# GPIO.net
KiCad netlist of a schematic drawn in Altium Designer
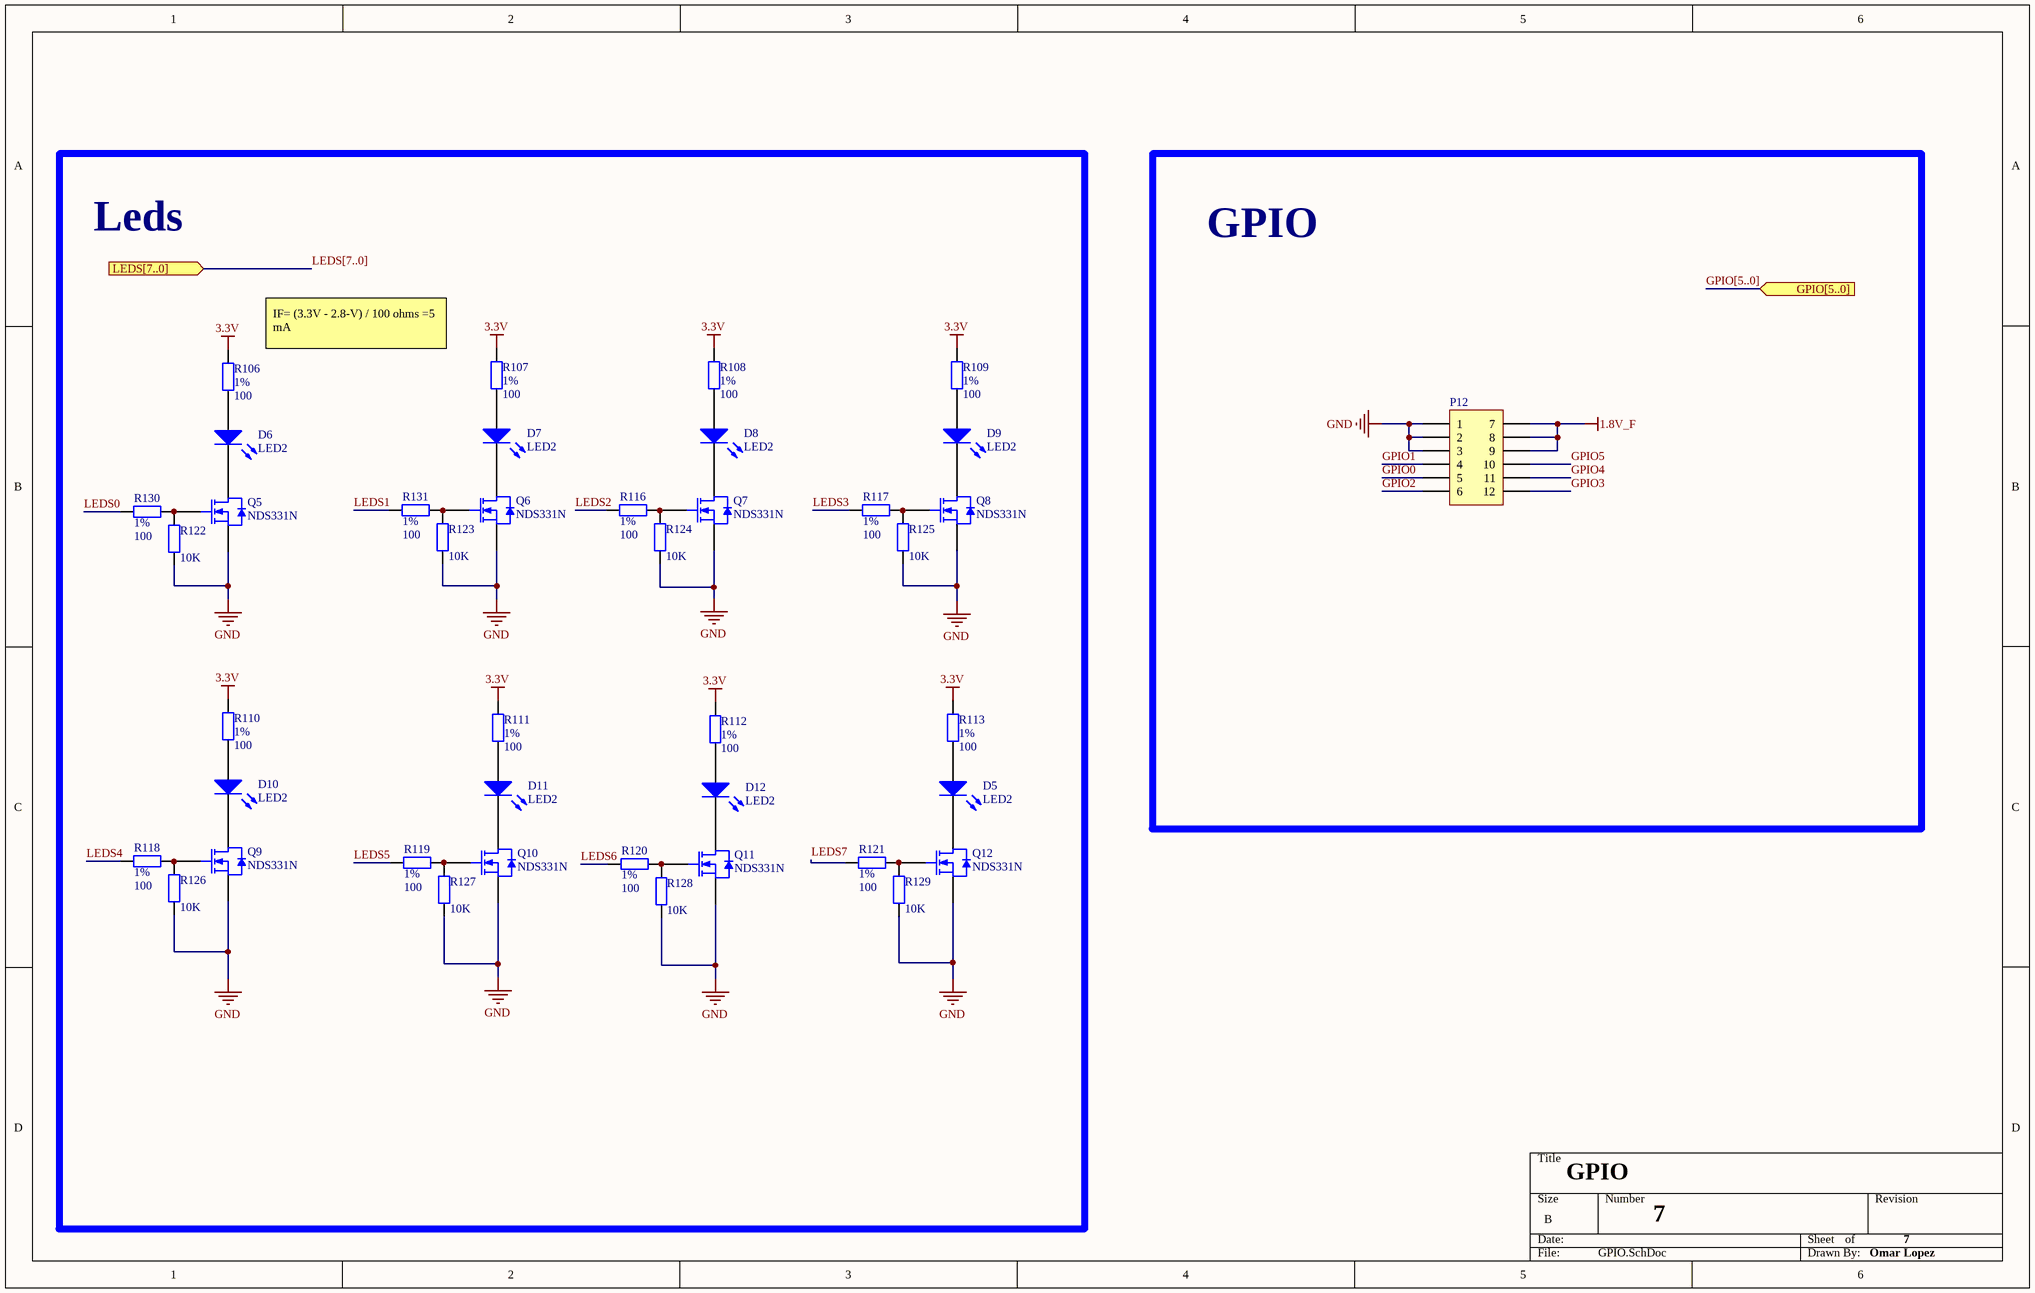
[diagram p0: GPIO.SchDoc]

(export (version "E")
  (design (tool "Eeschema 10.0.6"))
  (components
    (comp (ref "D5")
      (value "LED2")
      (footprint "LiteOnLed:LTSTC191")
      (description "Typical RED, GREEN, YELLOW, AMBER GaAs LED")
      (fields (field (name "MANUFACTURER") "Panasonic") (field (name "PARTNUMBER") "LTST-C193TGKT-5A"))
      (libsource (lib "Miscellaneous Devices") (part "LED2"))
    )
    (comp (ref "D6")
      (value "LED2")
      (footprint "LiteOnLed:LTSTC191")
      (description "Typical RED, GREEN, YELLOW, AMBER GaAs LED")
      (fields (field (name "MANUFACTURER") "Panasonic") (field (name "PARTNUMBER") "LTST-C193TGKT-5A"))
      (libsource (lib "Miscellaneous Devices") (part "LED2"))
    )
    (comp (ref "D7")
      (value "LED2")
      (footprint "LiteOnLed:LTSTC191")
      (description "Typical RED, GREEN, YELLOW, AMBER GaAs LED")
      (fields (field (name "MANUFACTURER") "Panasonic") (field (name "PARTNUMBER") "LTST-C193TGKT-5A"))
      (libsource (lib "Miscellaneous Devices") (part "LED2"))
    )
    (comp (ref "D8")
      (value "LED2")
      (footprint "LiteOnLed:LTSTC191")
      (description "Typical RED, GREEN, YELLOW, AMBER GaAs LED")
      (fields (field (name "MANUFACTURER") "Panasonic") (field (name "PARTNUMBER") "LTST-C193TGKT-5A"))
      (libsource (lib "Miscellaneous Devices") (part "LED2"))
    )
    (comp (ref "D9")
      (value "LED2")
      (footprint "LiteOnLed:LTSTC191")
      (description "Typical RED, GREEN, YELLOW, AMBER GaAs LED")
      (fields (field (name "MANUFACTURER") "Panasonic") (field (name "PARTNUMBER") "LTST-C193TGKT-5A"))
      (libsource (lib "Miscellaneous Devices") (part "LED2"))
    )
    (comp (ref "D10")
      (value "LED2")
      (footprint "LiteOnLed:LTSTC191")
      (description "Typical RED, GREEN, YELLOW, AMBER GaAs LED")
      (fields (field (name "MANUFACTURER") "Panasonic") (field (name "PARTNUMBER") "LTST-C193TGKT-5A"))
      (libsource (lib "Miscellaneous Devices") (part "LED2"))
    )
    (comp (ref "D11")
      (value "LED2")
      (footprint "LiteOnLed:LTSTC191")
      (description "Typical RED, GREEN, YELLOW, AMBER GaAs LED")
      (fields (field (name "MANUFACTURER") "Panasonic") (field (name "PARTNUMBER") "LTST-C193TGKT-5A"))
      (libsource (lib "Miscellaneous Devices") (part "LED2"))
    )
    (comp (ref "D12")
      (value "LED2")
      (footprint "LiteOnLed:LTSTC191")
      (description "Typical RED, GREEN, YELLOW, AMBER GaAs LED")
      (fields (field (name "MANUFACTURER") "Panasonic") (field (name "PARTNUMBER") "LTST-C193TGKT-5A"))
      (libsource (lib "Miscellaneous Devices") (part "LED2"))
    )
    (comp (ref "P12")
      (value "~")
      (footprint "PPTC062LJBN-RC:PPTC062LJBN-RC")
      (description "Header, 6-Pin, Dual row")
      (fields
        (field (name "MANUFACTURER") "Sullins Connector Solutions")
        (field (name "PARTNUMBER") "PPTC062LJBN-RC")
      )
      (libsource (lib "Miscellaneous Connectors") (part "Header 6X2A"))
    )
    (comp (ref "Q5")
      (value "NDS331N")
      (footprint "ON_Semi_527AG-01_0")
      (description "N-Channel 60V (D-S), 175'C  MOSFET")
      (fields (field (name "MANUFACTURER") "On Semiconductor"))
      (libsource (lib "Vishay Siliconix Discrete MOSFET") (part "SUP70N06-14"))
    )
    (comp (ref "Q6")
      (value "NDS331N")
      (footprint "ON_Semi_527AG-01_0")
      (description "N-Channel 60V (D-S), 175'C  MOSFET")
      (fields (field (name "MANUFACTURER") "On Semiconductor"))
      (libsource (lib "Vishay Siliconix Discrete MOSFET") (part "SUP70N06-14"))
    )
    (comp (ref "Q7")
      (value "NDS331N")
      (footprint "ON_Semi_527AG-01_0")
      (description "N-Channel 60V (D-S), 175'C  MOSFET")
      (fields (field (name "MANUFACTURER") "On Semiconductor"))
      (libsource (lib "Vishay Siliconix Discrete MOSFET") (part "SUP70N06-14"))
    )
    (comp (ref "Q8")
      (value "NDS331N")
      (footprint "ON_Semi_527AG-01_0")
      (description "N-Channel 60V (D-S), 175'C  MOSFET")
      (fields (field (name "MANUFACTURER") "On Semiconductor"))
      (libsource (lib "Vishay Siliconix Discrete MOSFET") (part "SUP70N06-14"))
    )
    (comp (ref "Q9")
      (value "NDS331N")
      (footprint "ON_Semi_527AG-01_0")
      (description "N-Channel 60V (D-S), 175'C  MOSFET")
      (fields (field (name "MANUFACTURER") "On Semiconductor"))
      (libsource (lib "Vishay Siliconix Discrete MOSFET") (part "SUP70N06-14"))
    )
    (comp (ref "Q10")
      (value "NDS331N")
      (footprint "ON_Semi_527AG-01_0")
      (description "N-Channel 60V (D-S), 175'C  MOSFET")
      (fields (field (name "MANUFACTURER") "On Semiconductor"))
      (libsource (lib "Vishay Siliconix Discrete MOSFET") (part "SUP70N06-14"))
    )
    (comp (ref "Q11")
      (value "NDS331N")
      (footprint "ON_Semi_527AG-01_0")
      (description "N-Channel 60V (D-S), 175'C  MOSFET")
      (fields (field (name "MANUFACTURER") "On Semiconductor"))
      (libsource (lib "Vishay Siliconix Discrete MOSFET") (part "SUP70N06-14"))
    )
    (comp (ref "Q12")
      (value "NDS331N")
      (footprint "ON_Semi_527AG-01_0")
      (description "N-Channel 60V (D-S), 175'C  MOSFET")
      (fields (field (name "MANUFACTURER") "On Semiconductor"))
      (libsource (lib "Vishay Siliconix Discrete MOSFET") (part "SUP70N06-14"))
    )
    (comp (ref "R106")
      (value "1%")
      (footprint "Res0402ERJ:RC0402N")
      (description "Resistor")
      (fields
        (field (name "ALTIUM_VALUE") "100")
        (field (name "MANUFACTURER") "Panasonic")
        (field (name "PARTNUMBER") "ERJ-2RKF4701X")
      )
      (libsource (lib "") (part "Res2_1"))
    )
    (comp (ref "R107")
      (value "1%")
      (footprint "Res0402ERJ:RC0402N")
      (description "Resistor")
      (fields
        (field (name "ALTIUM_VALUE") "100")
        (field (name "MANUFACTURER") "Panasonic")
        (field (name "PARTNUMBER") "ERJ-2RKF4701X")
      )
      (libsource (lib "") (part "Res2_1"))
    )
    (comp (ref "R108")
      (value "1%")
      (footprint "Res0402ERJ:RC0402N")
      (description "Resistor")
      (fields
        (field (name "ALTIUM_VALUE") "100")
        (field (name "MANUFACTURER") "Panasonic")
        (field (name "PARTNUMBER") "ERJ-2RKF4701X")
      )
      (libsource (lib "") (part "Res2_1"))
    )
    (comp (ref "R109")
      (value "1%")
      (footprint "Res0402ERJ:RC0402N")
      (description "Resistor")
      (fields
        (field (name "ALTIUM_VALUE") "100")
        (field (name "MANUFACTURER") "Panasonic")
        (field (name "PARTNUMBER") "ERJ-2RKF4701X")
      )
      (libsource (lib "") (part "Res2_1"))
    )
    (comp (ref "R110")
      (value "1%")
      (footprint "Res0402ERJ:RC0402N")
      (description "Resistor")
      (fields
        (field (name "ALTIUM_VALUE") "100")
        (field (name "MANUFACTURER") "Panasonic")
        (field (name "PARTNUMBER") "ERJ-2RKF4701X")
      )
      (libsource (lib "") (part "Res2_1"))
    )
    (comp (ref "R111")
      (value "1%")
      (footprint "Res0402ERJ:RC0402N")
      (description "Resistor")
      (fields
        (field (name "ALTIUM_VALUE") "100")
        (field (name "MANUFACTURER") "Panasonic")
        (field (name "PARTNUMBER") "ERJ-2RKF4701X")
      )
      (libsource (lib "") (part "Res2_1"))
    )
    (comp (ref "R112")
      (value "1%")
      (footprint "Res0402ERJ:RC0402N")
      (description "Resistor")
      (fields
        (field (name "ALTIUM_VALUE") "100")
        (field (name "MANUFACTURER") "Panasonic")
        (field (name "PARTNUMBER") "ERJ-2RKF4701X")
      )
      (libsource (lib "") (part "Res2_1"))
    )
    (comp (ref "R113")
      (value "1%")
      (footprint "Res0402ERJ:RC0402N")
      (description "Resistor")
      (fields
        (field (name "ALTIUM_VALUE") "100")
        (field (name "MANUFACTURER") "Panasonic")
        (field (name "PARTNUMBER") "ERJ-2RKF4701X")
      )
      (libsource (lib "") (part "Res2_1"))
    )
    (comp (ref "R116")
      (value "1%")
      (footprint "Res0402ERJ:RC0402N")
      (description "Resistor")
      (fields
        (field (name "ALTIUM_VALUE") "100")
        (field (name "MANUFACTURER") "Panasonic")
        (field (name "PARTNUMBER") "ERJ-2RKF4701X")
      )
      (libsource (lib "Miscellaneous Devices") (part "Res2"))
    )
    (comp (ref "R117")
      (value "1%")
      (footprint "Res0402ERJ:RC0402N")
      (description "Resistor")
      (fields
        (field (name "ALTIUM_VALUE") "100")
        (field (name "MANUFACTURER") "Panasonic")
        (field (name "PARTNUMBER") "ERJ-2RKF4701X")
      )
      (libsource (lib "Miscellaneous Devices") (part "Res2"))
    )
    (comp (ref "R118")
      (value "1%")
      (footprint "Res0402ERJ:RC0402N")
      (description "Resistor")
      (fields
        (field (name "ALTIUM_VALUE") "100")
        (field (name "MANUFACTURER") "Panasonic")
        (field (name "PARTNUMBER") "ERJ-2RKF4701X")
      )
      (libsource (lib "Miscellaneous Devices") (part "Res2"))
    )
    (comp (ref "R119")
      (value "1%")
      (footprint "Res0402ERJ:RC0402N")
      (description "Resistor")
      (fields
        (field (name "ALTIUM_VALUE") "100")
        (field (name "MANUFACTURER") "Panasonic")
        (field (name "PARTNUMBER") "ERJ-2RKF4701X")
      )
      (libsource (lib "Miscellaneous Devices") (part "Res2"))
    )
    (comp (ref "R120")
      (value "1%")
      (footprint "Res0402ERJ:RC0402N")
      (description "Resistor")
      (fields
        (field (name "ALTIUM_VALUE") "100")
        (field (name "MANUFACTURER") "Panasonic")
        (field (name "PARTNUMBER") "ERJ-2RKF4701X")
      )
      (libsource (lib "Miscellaneous Devices") (part "Res2"))
    )
    (comp (ref "R121")
      (value "1%")
      (footprint "Res0402ERJ:RC0402N")
      (description "Resistor")
      (fields
        (field (name "ALTIUM_VALUE") "100")
        (field (name "MANUFACTURER") "Panasonic")
        (field (name "PARTNUMBER") "ERJ-2RKF4701X")
      )
      (libsource (lib "Miscellaneous Devices") (part "Res2"))
    )
    (comp (ref "R122")
      (value "10K")
      (footprint "Res0402ERJ:RC0402N")
      (description "Resistor")
      (fields (field (name "MANUFACTURER") "Panasonic") (field (name "TOLERANCE") "1%"))
      (libsource (lib "") (part "Res2_2"))
    )
    (comp (ref "R123")
      (value "10K")
      (footprint "Res0402ERJ:RC0402N")
      (description "Resistor")
      (fields (field (name "MANUFACTURER") "Panasonic") (field (name "TOLERANCE") "1%"))
      (libsource (lib "") (part "Res2_2"))
    )
    (comp (ref "R124")
      (value "10K")
      (footprint "Res0402ERJ:RC0402N")
      (description "Resistor")
      (fields (field (name "MANUFACTURER") "Panasonic") (field (name "TOLERANCE") "1%"))
      (libsource (lib "") (part "Res2_2"))
    )
    (comp (ref "R125")
      (value "10K")
      (footprint "Res0402ERJ:RC0402N")
      (description "Resistor")
      (fields (field (name "MANUFACTURER") "Panasonic") (field (name "TOLERANCE") "1%"))
      (libsource (lib "") (part "Res2_2"))
    )
    (comp (ref "R126")
      (value "10K")
      (footprint "Res0402ERJ:RC0402N")
      (description "Resistor")
      (fields (field (name "MANUFACTURER") "Panasonic") (field (name "TOLERANCE") "1%"))
      (libsource (lib "") (part "Res2_2"))
    )
    (comp (ref "R127")
      (value "10K")
      (footprint "Res0402ERJ:RC0402N")
      (description "Resistor")
      (fields (field (name "MANUFACTURER") "Panasonic") (field (name "TOLERANCE") "1%"))
      (libsource (lib "") (part "Res2_2"))
    )
    (comp (ref "R128")
      (value "10K")
      (footprint "Res0402ERJ:RC0402N")
      (description "Resistor")
      (fields (field (name "MANUFACTURER") "Panasonic") (field (name "TOLERANCE") "1%"))
      (libsource (lib "") (part "Res2_2"))
    )
    (comp (ref "R129")
      (value "10K")
      (footprint "Res0402ERJ:RC0402N")
      (description "Resistor")
      (fields (field (name "MANUFACTURER") "Panasonic") (field (name "TOLERANCE") "1%"))
      (libsource (lib "") (part "Res2_2"))
    )
    (comp (ref "R130")
      (value "1%")
      (footprint "Res0402ERJ:RC0402N")
      (description "Resistor")
      (fields
        (field (name "ALTIUM_VALUE") "100")
        (field (name "MANUFACTURER") "Panasonic")
        (field (name "PARTNUMBER") "ERJ-2RKF4701X")
      )
      (libsource (lib "Miscellaneous Devices") (part "Res2"))
    )
    (comp (ref "R131")
      (value "1%")
      (footprint "Res0402ERJ:RC0402N")
      (description "Resistor")
      (fields
        (field (name "ALTIUM_VALUE") "100")
        (field (name "MANUFACTURER") "Panasonic")
        (field (name "PARTNUMBER") "ERJ-2RKF4701X")
      )
      (libsource (lib "Miscellaneous Devices") (part "Res2"))
    )
  )
  (nets
    (net (code "1") (name "/GPIO0") (class "Default")
      (node (ref "P12") (pin "5") (pinfunction "5_5") (pintype "passive"))
    )
    (net (code "2") (name "/GPIO1") (class "Default")
      (node (ref "P12") (pin "4") (pinfunction "4_4") (pintype "passive"))
    )
    (net (code "3") (name "/GPIO2") (class "Default")
      (node (ref "P12") (pin "6") (pinfunction "6_6") (pintype "passive"))
    )
    (net (code "4") (name "/GPIO3") (class "Default")
      (node (ref "P12") (pin "12") (pinfunction "12_12") (pintype "passive"))
    )
    (net (code "5") (name "/GPIO4") (class "Default")
      (node (ref "P12") (pin "11") (pinfunction "11_11") (pintype "passive"))
    )
    (net (code "6") (name "/GPIO5") (class "Default")
      (node (ref "P12") (pin "10") (pinfunction "10_10") (pintype "passive"))
    )
    (net (code "8") (name "/LEDS0") (class "Default")
      (node (ref "R130") (pin "2") (pinfunction "2_2") (pintype "passive"))
    )
    (net (code "9") (name "/LEDS1") (class "Default")
      (node (ref "R131") (pin "2") (pinfunction "2_2") (pintype "passive"))
    )
    (net (code "10") (name "/LEDS2") (class "Default")
      (node (ref "R116") (pin "2") (pinfunction "2_2") (pintype "passive"))
    )
    (net (code "11") (name "/LEDS3") (class "Default")
      (node (ref "R117") (pin "2") (pinfunction "2_2") (pintype "passive"))
    )
    (net (code "12") (name "/LEDS4") (class "Default")
      (node (ref "R118") (pin "2") (pinfunction "2_2") (pintype "passive"))
    )
    (net (code "13") (name "/LEDS5") (class "Default")
      (node (ref "R119") (pin "2") (pinfunction "2_2") (pintype "passive"))
    )
    (net (code "14") (name "/LEDS6") (class "Default")
      (node (ref "R120") (pin "2") (pinfunction "2_2") (pintype "passive"))
    )
    (net (code "15") (name "/LEDS7") (class "Default")
      (node (ref "R121") (pin "2") (pinfunction "2_2") (pintype "passive"))
    )
    (net (code "17") (name "1.8V_F") (class "Default")
      (node (ref "P12") (pin "7") (pinfunction "7_7") (pintype "passive"))
      (node (ref "P12") (pin "8") (pinfunction "8_8") (pintype "passive"))
      (node (ref "P12") (pin "9") (pinfunction "9_9") (pintype "passive"))
    )
    (net (code "18") (name "3.3V") (class "Default")
      (node (ref "R106") (pin "2") (pinfunction "2_2") (pintype "passive"))
      (node (ref "R107") (pin "2") (pinfunction "2_2") (pintype "passive"))
      (node (ref "R108") (pin "2") (pinfunction "2_2") (pintype "passive"))
      (node (ref "R109") (pin "2") (pinfunction "2_2") (pintype "passive"))
      (node (ref "R110") (pin "2") (pinfunction "2_2") (pintype "passive"))
      (node (ref "R111") (pin "2") (pinfunction "2_2") (pintype "passive"))
      (node (ref "R112") (pin "2") (pinfunction "2_2") (pintype "passive"))
      (node (ref "R113") (pin "2") (pinfunction "2_2") (pintype "passive"))
    )
    (net (code "19") (name "GND") (class "Default")
      (node (ref "P12") (pin "1") (pinfunction "1_1") (pintype "passive"))
      (node (ref "P12") (pin "2") (pinfunction "2_2") (pintype "passive"))
      (node (ref "P12") (pin "3") (pinfunction "3_3") (pintype "passive"))
      (node (ref "Q10") (pin "3") (pinfunction "S_3") (pintype "passive"))
      (node (ref "Q11") (pin "3") (pinfunction "S_3") (pintype "passive"))
      (node (ref "Q12") (pin "3") (pinfunction "S_3") (pintype "passive"))
      (node (ref "Q5") (pin "3") (pinfunction "S_3") (pintype "passive"))
      (node (ref "Q6") (pin "3") (pinfunction "S_3") (pintype "passive"))
      (node (ref "Q7") (pin "3") (pinfunction "S_3") (pintype "passive"))
      (node (ref "Q8") (pin "3") (pinfunction "S_3") (pintype "passive"))
      (node (ref "Q9") (pin "3") (pinfunction "S_3") (pintype "passive"))
      (node (ref "R122") (pin "2") (pinfunction "2_2") (pintype "passive"))
      (node (ref "R123") (pin "2") (pinfunction "2_2") (pintype "passive"))
      (node (ref "R124") (pin "2") (pinfunction "2_2") (pintype "passive"))
      (node (ref "R125") (pin "2") (pinfunction "2_2") (pintype "passive"))
      (node (ref "R126") (pin "2") (pinfunction "2_2") (pintype "passive"))
      (node (ref "R127") (pin "2") (pinfunction "2_2") (pintype "passive"))
      (node (ref "R128") (pin "2") (pinfunction "2_2") (pintype "passive"))
      (node (ref "R129") (pin "2") (pinfunction "2_2") (pintype "passive"))
    )
    (net (code "20") (name "Net-(D5-A)") (class "Default")
      (node (ref "D5") (pin "1") (pinfunction "A_1") (pintype "passive"))
      (node (ref "R113") (pin "1") (pinfunction "1_1") (pintype "passive"))
    )
    (net (code "21") (name "Net-(D5-K)") (class "Default")
      (node (ref "D5") (pin "2") (pinfunction "K_2") (pintype "passive"))
      (node (ref "Q12") (pin "2") (pinfunction "D_2") (pintype "passive"))
    )
    (net (code "22") (name "Net-(D6-A)") (class "Default")
      (node (ref "D6") (pin "1") (pinfunction "A_1") (pintype "passive"))
      (node (ref "R106") (pin "1") (pinfunction "1_1") (pintype "passive"))
    )
    (net (code "23") (name "Net-(D6-K)") (class "Default")
      (node (ref "D6") (pin "2") (pinfunction "K_2") (pintype "passive"))
      (node (ref "Q5") (pin "2") (pinfunction "D_2") (pintype "passive"))
    )
    (net (code "24") (name "Net-(D7-A)") (class "Default")
      (node (ref "D7") (pin "1") (pinfunction "A_1") (pintype "passive"))
      (node (ref "R107") (pin "1") (pinfunction "1_1") (pintype "passive"))
    )
    (net (code "25") (name "Net-(D7-K)") (class "Default")
      (node (ref "D7") (pin "2") (pinfunction "K_2") (pintype "passive"))
      (node (ref "Q6") (pin "2") (pinfunction "D_2") (pintype "passive"))
    )
    (net (code "26") (name "Net-(D8-A)") (class "Default")
      (node (ref "D8") (pin "1") (pinfunction "A_1") (pintype "passive"))
      (node (ref "R108") (pin "1") (pinfunction "1_1") (pintype "passive"))
    )
    (net (code "27") (name "Net-(D8-K)") (class "Default")
      (node (ref "D8") (pin "2") (pinfunction "K_2") (pintype "passive"))
      (node (ref "Q7") (pin "2") (pinfunction "D_2") (pintype "passive"))
    )
    (net (code "28") (name "Net-(D9-A)") (class "Default")
      (node (ref "D9") (pin "1") (pinfunction "A_1") (pintype "passive"))
      (node (ref "R109") (pin "1") (pinfunction "1_1") (pintype "passive"))
    )
    (net (code "29") (name "Net-(D9-K)") (class "Default")
      (node (ref "D9") (pin "2") (pinfunction "K_2") (pintype "passive"))
      (node (ref "Q8") (pin "2") (pinfunction "D_2") (pintype "passive"))
    )
    (net (code "30") (name "Net-(D10-A)") (class "Default")
      (node (ref "D10") (pin "1") (pinfunction "A_1") (pintype "passive"))
      (node (ref "R110") (pin "1") (pinfunction "1_1") (pintype "passive"))
    )
    (net (code "31") (name "Net-(D10-K)") (class "Default")
      (node (ref "D10") (pin "2") (pinfunction "K_2") (pintype "passive"))
      (node (ref "Q9") (pin "2") (pinfunction "D_2") (pintype "passive"))
    )
    (net (code "32") (name "Net-(D11-A)") (class "Default")
      (node (ref "D11") (pin "1") (pinfunction "A_1") (pintype "passive"))
      (node (ref "R111") (pin "1") (pinfunction "1_1") (pintype "passive"))
    )
    (net (code "33") (name "Net-(D11-K)") (class "Default")
      (node (ref "D11") (pin "2") (pinfunction "K_2") (pintype "passive"))
      (node (ref "Q10") (pin "2") (pinfunction "D_2") (pintype "passive"))
    )
    (net (code "34") (name "Net-(D12-A)") (class "Default")
      (node (ref "D12") (pin "1") (pinfunction "A_1") (pintype "passive"))
      (node (ref "R112") (pin "1") (pinfunction "1_1") (pintype "passive"))
    )
    (net (code "35") (name "Net-(D12-K)") (class "Default")
      (node (ref "D12") (pin "2") (pinfunction "K_2") (pintype "passive"))
      (node (ref "Q11") (pin "2") (pinfunction "D_2") (pintype "passive"))
    )
    (net (code "36") (name "Net-(Q5-G)") (class "Default")
      (node (ref "Q5") (pin "1") (pinfunction "G_1") (pintype "passive"))
      (node (ref "R122") (pin "1") (pinfunction "1_1") (pintype "passive"))
      (node (ref "R130") (pin "1") (pinfunction "1_1") (pintype "passive"))
    )
    (net (code "37") (name "Net-(Q6-G)") (class "Default")
      (node (ref "Q6") (pin "1") (pinfunction "G_1") (pintype "passive"))
      (node (ref "R123") (pin "1") (pinfunction "1_1") (pintype "passive"))
      (node (ref "R131") (pin "1") (pinfunction "1_1") (pintype "passive"))
    )
    (net (code "38") (name "Net-(Q7-G)") (class "Default")
      (node (ref "Q7") (pin "1") (pinfunction "G_1") (pintype "passive"))
      (node (ref "R116") (pin "1") (pinfunction "1_1") (pintype "passive"))
      (node (ref "R124") (pin "1") (pinfunction "1_1") (pintype "passive"))
    )
    (net (code "39") (name "Net-(Q8-G)") (class "Default")
      (node (ref "Q8") (pin "1") (pinfunction "G_1") (pintype "passive"))
      (node (ref "R117") (pin "1") (pinfunction "1_1") (pintype "passive"))
      (node (ref "R125") (pin "1") (pinfunction "1_1") (pintype "passive"))
    )
    (net (code "40") (name "Net-(Q9-G)") (class "Default")
      (node (ref "Q9") (pin "1") (pinfunction "G_1") (pintype "passive"))
      (node (ref "R118") (pin "1") (pinfunction "1_1") (pintype "passive"))
      (node (ref "R126") (pin "1") (pinfunction "1_1") (pintype "passive"))
    )
    (net (code "41") (name "Net-(Q10-G)") (class "Default")
      (node (ref "Q10") (pin "1") (pinfunction "G_1") (pintype "passive"))
      (node (ref "R119") (pin "1") (pinfunction "1_1") (pintype "passive"))
      (node (ref "R127") (pin "1") (pinfunction "1_1") (pintype "passive"))
    )
    (net (code "42") (name "Net-(Q11-G)") (class "Default")
      (node (ref "Q11") (pin "1") (pinfunction "G_1") (pintype "passive"))
      (node (ref "R120") (pin "1") (pinfunction "1_1") (pintype "passive"))
      (node (ref "R128") (pin "1") (pinfunction "1_1") (pintype "passive"))
    )
    (net (code "43") (name "Net-(Q12-G)") (class "Default")
      (node (ref "Q12") (pin "1") (pinfunction "G_1") (pintype "passive"))
      (node (ref "R121") (pin "1") (pinfunction "1_1") (pintype "passive"))
      (node (ref "R129") (pin "1") (pinfunction "1_1") (pintype "passive"))
    )
  )
)
